# touch_sensor3.net
KiCad netlist of a schematic drawn in EAGLE
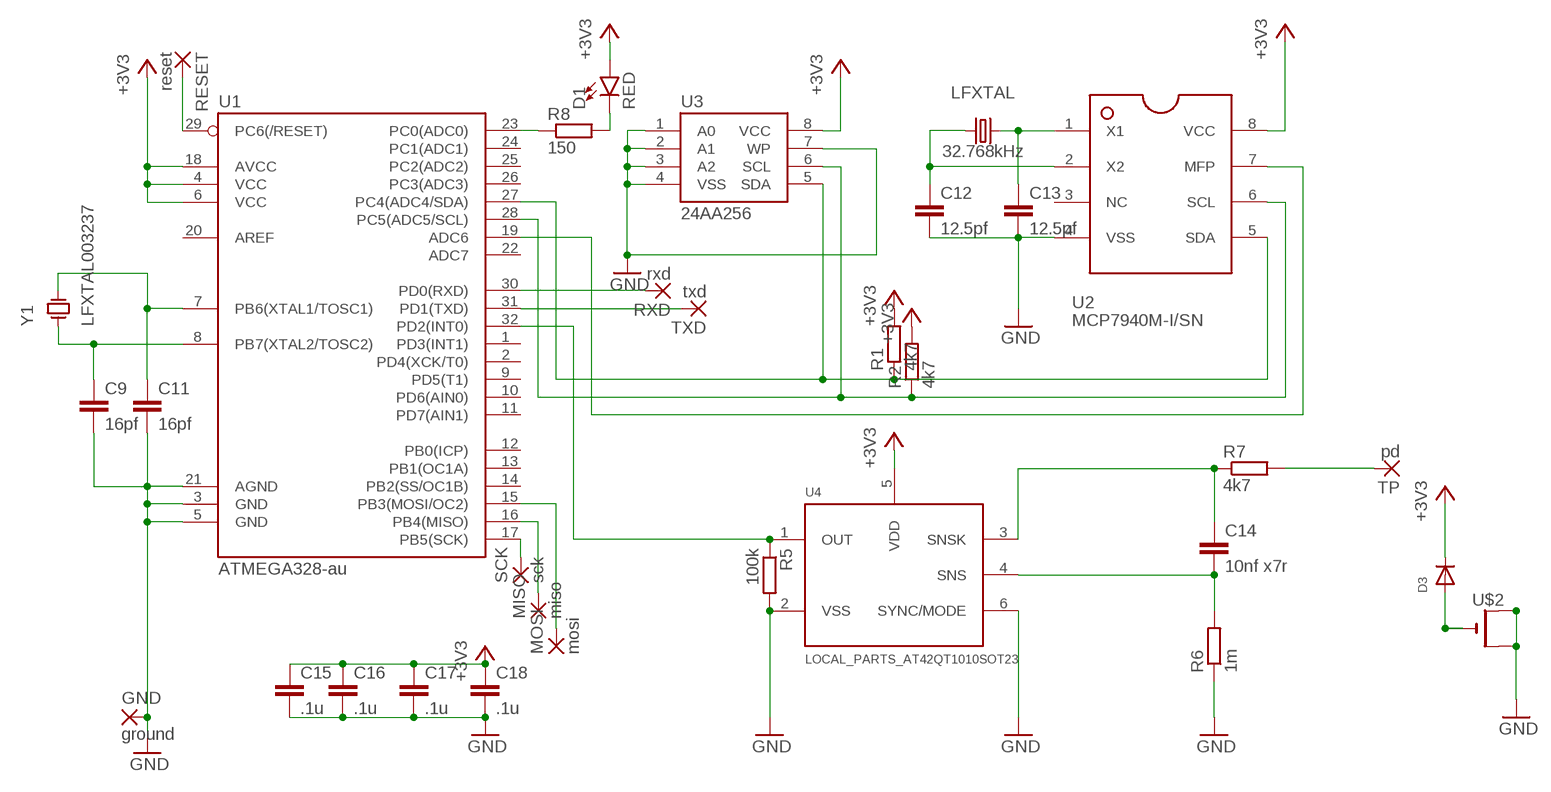
[diagram p0: schematic, sheet 1]

(export (version "E")
  (design (tool "Eeschema 10.0.6"))
  (components
    (comp (ref "C9")
      (value "16pf")
      (footprint "eagle-import:C0805")
      (libsource (lib "eagle-import") (part "C-EUC0805"))
    )
    (comp (ref "C11")
      (value "16pf")
      (footprint "eagle-import:C0805")
      (libsource (lib "eagle-import") (part "C-EUC0805"))
    )
    (comp (ref "C12")
      (value "12.5pf")
      (footprint "eagle-import:C0805")
      (libsource (lib "eagle-import") (part "C-EUC0805"))
    )
    (comp (ref "C13")
      (value "12.5pf")
      (footprint "eagle-import:C0805")
      (libsource (lib "eagle-import") (part "C-EUC0805"))
    )
    (comp (ref "C14")
      (value "10nf x7r")
      (footprint "eagle-import:C0805")
      (libsource (lib "eagle-import") (part "C-EUC0805"))
    )
    (comp (ref "C15")
      (value ".1u")
      (footprint "eagle-import:C0805")
      (libsource (lib "eagle-import") (part "C-EUC0805"))
    )
    (comp (ref "C16")
      (value ".1u")
      (footprint "eagle-import:C0805")
      (libsource (lib "eagle-import") (part "C-EUC0805"))
    )
    (comp (ref "C17")
      (value ".1u")
      (footprint "eagle-import:C0805")
      (libsource (lib "eagle-import") (part "C-EUC0805"))
    )
    (comp (ref "C18")
      (value ".1u")
      (footprint "eagle-import:C0805")
      (libsource (lib "eagle-import") (part "C-EUC0805"))
    )
    (comp (ref "D1")
      (value "RED")
      (footprint "eagle-import:LED-0603")
      (libsource (lib "eagle-import") (part "LED-RED0603"))
    )
    (comp (ref "D3")
      (value "DIODESMA")
      (footprint "eagle-import:SMADIODE")
      (libsource (lib "eagle-import") (part "DIODESMA"))
    )
    (comp (ref "GND")
      (value "ground")
      (footprint "eagle-import:SMD1,27-2,54")
      (libsource (lib "eagle-import") (part "WIREPADSMD1,27-254"))
    )
    (comp (ref "LFXTAL")
      (value "32.768kHz")
      (footprint "eagle-import:CRYSTAL-PTH-2X6-CYL")
      (libsource (lib "eagle-import") (part "CRYSTAL-32.768KHZPTH-2X6"))
    )
    (comp (ref "MISO")
      (value "miso")
      (footprint "eagle-import:SMD1,27-2,54")
      (libsource (lib "eagle-import") (part "WIREPADSMD1,27-254"))
    )
    (comp (ref "MOSI")
      (value "mosi")
      (footprint "eagle-import:SMD1,27-2,54")
      (libsource (lib "eagle-import") (part "WIREPADSMD1,27-254"))
    )
    (comp (ref "R1")
      (value "4k7")
      (footprint "eagle-import:M0805")
      (libsource (lib "eagle-import") (part "R-EU_M0805"))
    )
    (comp (ref "R2")
      (value "4k7")
      (footprint "eagle-import:M0805")
      (libsource (lib "eagle-import") (part "R-EU_M0805"))
    )
    (comp (ref "R5")
      (value "100k")
      (footprint "eagle-import:R0805")
      (libsource (lib "eagle-import") (part "R-EU_R0805"))
    )
    (comp (ref "R6")
      (value "1m")
      (footprint "eagle-import:R0805")
      (libsource (lib "eagle-import") (part "R-EU_R0805"))
    )
    (comp (ref "R7")
      (value "4k7")
      (footprint "eagle-import:R0805")
      (libsource (lib "eagle-import") (part "R-EU_R0805"))
    )
    (comp (ref "R8")
      (value "150")
      (footprint "eagle-import:R0805")
      (libsource (lib "eagle-import") (part "R-EU_R0805"))
    )
    (comp (ref "RESET")
      (value "reset")
      (footprint "eagle-import:SMD1,27-2,54")
      (libsource (lib "eagle-import") (part "WIREPADSMD1,27-254"))
    )
    (comp (ref "RXD")
      (value "rxd")
      (footprint "eagle-import:SMD1,27-2,54")
      (libsource (lib "eagle-import") (part "WIREPADSMD1,27-254"))
    )
    (comp (ref "SCK")
      (value "sck")
      (footprint "eagle-import:SMD1,27-2,54")
      (libsource (lib "eagle-import") (part "WIREPADSMD1,27-254"))
    )
    (comp (ref "TP")
      (value "pd")
      (footprint "eagle-import:SMD1,27-2,54")
      (libsource (lib "eagle-import") (part "WIREPADSMD1,27-254"))
    )
    (comp (ref "TXD")
      (value "txd")
      (footprint "eagle-import:SMD1,27-2,54")
      (libsource (lib "eagle-import") (part "WIREPADSMD1,27-254"))
    )
    (comp (ref "U$2")
      (value "CR2032SMT")
      (footprint "eagle-import:CR2032-SMD")
      (libsource (lib "eagle-import") (part "CR2032SMT"))
    )
    (comp (ref "U1")
      (value "ATMEGA328-au")
      (footprint "eagle-import:TQFP32-08")
      (libsource (lib "eagle-import") (part "ATMEGA328P_TQFP"))
    )
    (comp (ref "U2")
      (value "MCP7940M-I/SN")
      (footprint "eagle-import:SO08")
      (fields (field (name "MF") "Microchip"))
      (libsource (lib "eagle-import") (part "MCP7940M-I/SN"))
    )
    (comp (ref "U3")
      (value "24AA256")
      (footprint "eagle-import:SO08")
      (libsource (lib "eagle-import") (part "EEPROM-I2CSMD"))
    )
    (comp (ref "U4")
      (value "LOCAL_PARTS_AT42QT1010SOT23")
      (footprint "eagle-import:LOCAL_PARTS_SOT23-6")
      (libsource (lib "eagle-import") (part "LOCAL_PARTS_AT42QT1010SOT23"))
    )
    (comp (ref "Y1")
      (value "LFXTAL003237")
      (footprint "eagle-import:XTAL1140X490X430N")
      (fields (field (name "MF") "IQD Frequency Products"))
      (libsource (lib "eagle-import") (part "LFXTAL003237"))
    )
  )
  (nets
    (net (code "1") (name "+3V3") (class "Default")
      (node (ref "C15") (pin "1") (pinfunction "1_1") (pintype "passive"))
      (node (ref "C16") (pin "1") (pinfunction "1_1") (pintype "passive"))
      (node (ref "C17") (pin "1") (pinfunction "1_1") (pintype "passive"))
      (node (ref "C18") (pin "1") (pinfunction "1_1") (pintype "passive"))
      (node (ref "D1") (pin "A") (pinfunction "A_A") (pintype "passive"))
      (node (ref "D3") (pin "C") (pinfunction "C_C") (pintype "passive"))
      (node (ref "R1") (pin "2") (pinfunction "2_2") (pintype "passive"))
      (node (ref "R2") (pin "2") (pinfunction "2_2") (pintype "passive"))
      (node (ref "U1") (pin "18") (pinfunction "AVCC_18") (pintype "bidirectional"))
      (node (ref "U1") (pin "4") (pinfunction "VCC_4") (pintype "bidirectional"))
      (node (ref "U1") (pin "6") (pinfunction "VCC_6") (pintype "bidirectional"))
      (node (ref "U2") (pin "8") (pinfunction "VCC_8") (pintype "power_in"))
      (node (ref "U3") (pin "8") (pinfunction "VCC_8") (pintype "power_in"))
      (node (ref "U4") (pin "5") (pinfunction "VDD_5") (pintype "bidirectional"))
    )
    (net (code "2") (name "GND") (class "Default")
      (node (ref "C11") (pin "2") (pinfunction "2_2") (pintype "passive"))
      (node (ref "C12") (pin "2") (pinfunction "2_2") (pintype "passive"))
      (node (ref "C13") (pin "2") (pinfunction "2_2") (pintype "passive"))
      (node (ref "C15") (pin "2") (pinfunction "2_2") (pintype "passive"))
      (node (ref "C16") (pin "2") (pinfunction "2_2") (pintype "passive"))
      (node (ref "C17") (pin "2") (pinfunction "2_2") (pintype "passive"))
      (node (ref "C18") (pin "2") (pinfunction "2_2") (pintype "passive"))
      (node (ref "C9") (pin "2") (pinfunction "2_2") (pintype "passive"))
      (node (ref "GND") (pin "1") (pinfunction "P_1") (pintype "passive"))
      (node (ref "R5") (pin "2") (pinfunction "2_2") (pintype "passive"))
      (node (ref "R6") (pin "1") (pinfunction "1_1") (pintype "passive"))
      (node (ref "U$2") (pin "+$1") (pinfunction "+_+$1") (pintype "passive"))
      (node (ref "U$2") (pin "+$2") (pinfunction "+1_+$2") (pintype "passive"))
      (node (ref "U1") (pin "21") (pinfunction "AGND_21") (pintype "bidirectional"))
      (node (ref "U1") (pin "3") (pinfunction "GND_3") (pintype "bidirectional"))
      (node (ref "U1") (pin "5") (pinfunction "GND_5") (pintype "bidirectional"))
      (node (ref "U2") (pin "4") (pinfunction "VSS_4") (pintype "passive"))
      (node (ref "U3") (pin "1") (pinfunction "A0_1") (pintype "bidirectional"))
      (node (ref "U3") (pin "2") (pinfunction "A1_2") (pintype "bidirectional"))
      (node (ref "U3") (pin "3") (pinfunction "A2_3") (pintype "bidirectional"))
      (node (ref "U3") (pin "4") (pinfunction "VSS_4") (pintype "power_in"))
      (node (ref "U3") (pin "7") (pinfunction "WP_7") (pintype "bidirectional"))
      (node (ref "U4") (pin "2") (pinfunction "VSS_2") (pintype "bidirectional"))
      (node (ref "U4") (pin "6") (pinfunction "SYNC/MODE_6") (pintype "bidirectional"))
    )
    (net (code "3") (name "Net-(D1-PadC)") (class "Default")
      (node (ref "D1") (pin "C") (pinfunction "C_C") (pintype "passive"))
      (node (ref "R8") (pin "2") (pinfunction "2_2") (pintype "passive"))
    )
    (net (code "4") (name "Net-(D3-PadA)") (class "Default")
      (node (ref "D3") (pin "A") (pinfunction "A_A") (pintype "passive"))
      (node (ref "U$2") (pin "-") (pinfunction "-_-") (pintype "passive"))
    )
    (net (code "5") (name "Net-(MISO-P)") (class "Default")
      (node (ref "MISO") (pin "1") (pinfunction "P_1") (pintype "passive"))
      (node (ref "U1") (pin "16") (pinfunction "PB4(MISO)_16") (pintype "bidirectional"))
    )
    (net (code "6") (name "Net-(MOSI-P)") (class "Default")
      (node (ref "MOSI") (pin "1") (pinfunction "P_1") (pintype "passive"))
      (node (ref "U1") (pin "15") (pinfunction "PB3(MOSI/OC2)_15") (pintype "bidirectional"))
    )
    (net (code "7") (name "Net-(RESET-P)") (class "Default")
      (node (ref "RESET") (pin "1") (pinfunction "P_1") (pintype "passive"))
      (node (ref "U1") (pin "29") (pinfunction "PC6(/RESET)_29") (pintype "bidirectional"))
    )
    (net (code "8") (name "Net-(RXD-P)") (class "Default")
      (node (ref "RXD") (pin "1") (pinfunction "P_1") (pintype "passive"))
      (node (ref "U1") (pin "30") (pinfunction "PD0(RXD)_30") (pintype "bidirectional"))
    )
    (net (code "9") (name "Net-(SCK-P)") (class "Default")
      (node (ref "SCK") (pin "1") (pinfunction "P_1") (pintype "passive"))
      (node (ref "U1") (pin "17") (pinfunction "PB5(SCK)_17") (pintype "bidirectional"))
    )
    (net (code "10") (name "Net-(TP-P)") (class "Default")
      (node (ref "R7") (pin "2") (pinfunction "2_2") (pintype "passive"))
      (node (ref "TP") (pin "1") (pinfunction "P_1") (pintype "passive"))
    )
    (net (code "11") (name "Net-(TXD-P)") (class "Default")
      (node (ref "TXD") (pin "1") (pinfunction "P_1") (pintype "passive"))
      (node (ref "U1") (pin "31") (pinfunction "PD1(TXD)_31") (pintype "bidirectional"))
    )
    (net (code "12") (name "Net-(U1-ADC6)") (class "Default")
      (node (ref "U1") (pin "19") (pinfunction "ADC6_19") (pintype "bidirectional"))
      (node (ref "U2") (pin "7") (pinfunction "MFP_7") (pintype "bidirectional"))
    )
    (net (code "13") (name "Net-(U1-PB6(XTAL1{slash}TOSC1))") (class "Default")
      (node (ref "C11") (pin "1") (pinfunction "1_1") (pintype "passive"))
      (node (ref "U1") (pin "7") (pinfunction "PB6(XTAL1/TOSC1)_7") (pintype "bidirectional"))
      (node (ref "Y1") (pin "2") (pinfunction "2_2") (pintype "passive"))
    )
    (net (code "14") (name "Net-(U1-PB7(XTAL2{slash}TOSC2))") (class "Default")
      (node (ref "C9") (pin "1") (pinfunction "1_1") (pintype "passive"))
      (node (ref "U1") (pin "8") (pinfunction "PB7(XTAL2/TOSC2)_8") (pintype "bidirectional"))
      (node (ref "Y1") (pin "1") (pinfunction "1_1") (pintype "passive"))
    )
    (net (code "15") (name "Net-(U1-PC0(ADC0))") (class "Default")
      (node (ref "R8") (pin "1") (pinfunction "1_1") (pintype "passive"))
      (node (ref "U1") (pin "23") (pinfunction "PC0(ADC0)_23") (pintype "bidirectional"))
    )
    (net (code "16") (name "Net-(U1-PC4(ADC4{slash}SDA))") (class "Default")
      (node (ref "R1") (pin "1") (pinfunction "1_1") (pintype "passive"))
      (node (ref "U1") (pin "27") (pinfunction "PC4(ADC4/SDA)_27") (pintype "bidirectional"))
      (node (ref "U2") (pin "5") (pinfunction "SDA_5") (pintype "bidirectional"))
      (node (ref "U3") (pin "5") (pinfunction "SDA_5") (pintype "bidirectional"))
    )
    (net (code "17") (name "Net-(U1-PC5(ADC5{slash}SCL))") (class "Default")
      (node (ref "R2") (pin "1") (pinfunction "1_1") (pintype "passive"))
      (node (ref "U1") (pin "28") (pinfunction "PC5(ADC5/SCL)_28") (pintype "bidirectional"))
      (node (ref "U2") (pin "6") (pinfunction "SCL_6") (pintype "input"))
      (node (ref "U3") (pin "6") (pinfunction "SCL_6") (pintype "bidirectional"))
    )
    (net (code "18") (name "Net-(U1-PD2(INT0))") (class "Default")
      (node (ref "R5") (pin "1") (pinfunction "1_1") (pintype "passive"))
      (node (ref "U1") (pin "32") (pinfunction "PD2(INT0)_32") (pintype "bidirectional"))
      (node (ref "U4") (pin "1") (pinfunction "OUT_1") (pintype "bidirectional"))
    )
    (net (code "19") (name "Net-(U2-X1)") (class "Default")
      (node (ref "C13") (pin "1") (pinfunction "1_1") (pintype "passive"))
      (node (ref "LFXTAL") (pin "2") (pinfunction "2_2") (pintype "passive"))
      (node (ref "U2") (pin "1") (pinfunction "X1_1") (pintype "input"))
    )
    (net (code "20") (name "Net-(U2-X2)") (class "Default")
      (node (ref "C12") (pin "1") (pinfunction "1_1") (pintype "passive"))
      (node (ref "LFXTAL") (pin "1") (pinfunction "1_1") (pintype "passive"))
      (node (ref "U2") (pin "2") (pinfunction "X2_2") (pintype "output"))
    )
    (net (code "21") (name "Net-(U4-SNS)") (class "Default")
      (node (ref "C14") (pin "2") (pinfunction "2_2") (pintype "passive"))
      (node (ref "R6") (pin "2") (pinfunction "2_2") (pintype "passive"))
      (node (ref "U4") (pin "4") (pinfunction "SNS_4") (pintype "bidirectional"))
    )
    (net (code "22") (name "Net-(U4-SNSK)") (class "Default")
      (node (ref "C14") (pin "1") (pinfunction "1_1") (pintype "passive"))
      (node (ref "R7") (pin "1") (pinfunction "1_1") (pintype "passive"))
      (node (ref "U4") (pin "3") (pinfunction "SNSK_3") (pintype "bidirectional"))
    )
    (net (code "23") (name "unconnected-(U1-ADC7-Pad22)") (class "Default")
      (node (ref "U1") (pin "22") (pinfunction "ADC7_22") (pintype "bidirectional"))
    )
    (net (code "24") (name "unconnected-(U1-AREF-Pad20)") (class "Default")
      (node (ref "U1") (pin "20") (pinfunction "AREF_20") (pintype "bidirectional"))
    )
    (net (code "25") (name "unconnected-(U1-PB0(ICP)-Pad12)") (class "Default")
      (node (ref "U1") (pin "12") (pinfunction "PB0(ICP)_12") (pintype "bidirectional"))
    )
    (net (code "26") (name "unconnected-(U1-PB1(OC1A)-Pad13)") (class "Default")
      (node (ref "U1") (pin "13") (pinfunction "PB1(OC1A)_13") (pintype "bidirectional"))
    )
    (net (code "27") (name "unconnected-(U1-PB2(SS{slash}OC1B)-Pad14)") (class "Default")
      (node (ref "U1") (pin "14") (pinfunction "PB2(SS/OC1B)_14") (pintype "bidirectional"))
    )
    (net (code "28") (name "unconnected-(U1-PC1(ADC1)-Pad24)") (class "Default")
      (node (ref "U1") (pin "24") (pinfunction "PC1(ADC1)_24") (pintype "bidirectional"))
    )
    (net (code "29") (name "unconnected-(U1-PC2(ADC2)-Pad25)") (class "Default")
      (node (ref "U1") (pin "25") (pinfunction "PC2(ADC2)_25") (pintype "bidirectional"))
    )
    (net (code "30") (name "unconnected-(U1-PC3(ADC3)-Pad26)") (class "Default")
      (node (ref "U1") (pin "26") (pinfunction "PC3(ADC3)_26") (pintype "bidirectional"))
    )
    (net (code "31") (name "unconnected-(U1-PD3(INT1)-Pad1)") (class "Default")
      (node (ref "U1") (pin "1") (pinfunction "PD3(INT1)_1") (pintype "bidirectional"))
    )
    (net (code "32") (name "unconnected-(U1-PD4(XCK{slash}T0)-Pad2)") (class "Default")
      (node (ref "U1") (pin "2") (pinfunction "PD4(XCK/T0)_2") (pintype "bidirectional"))
    )
    (net (code "33") (name "unconnected-(U1-PD5(T1)-Pad9)") (class "Default")
      (node (ref "U1") (pin "9") (pinfunction "PD5(T1)_9") (pintype "bidirectional"))
    )
    (net (code "34") (name "unconnected-(U1-PD6(AIN0)-Pad10)") (class "Default")
      (node (ref "U1") (pin "10") (pinfunction "PD6(AIN0)_10") (pintype "bidirectional"))
    )
    (net (code "35") (name "unconnected-(U1-PD7(AIN1)-Pad11)") (class "Default")
      (node (ref "U1") (pin "11") (pinfunction "PD7(AIN1)_11") (pintype "bidirectional"))
    )
    (net (code "36") (name "unconnected-(U2-NC-Pad3)") (class "Default")
      (node (ref "U2") (pin "3") (pinfunction "NC_3") (pintype "passive"))
    )
  )
)
